# untitled.net
KiCad netlist of a schematic drawn in EAGLE
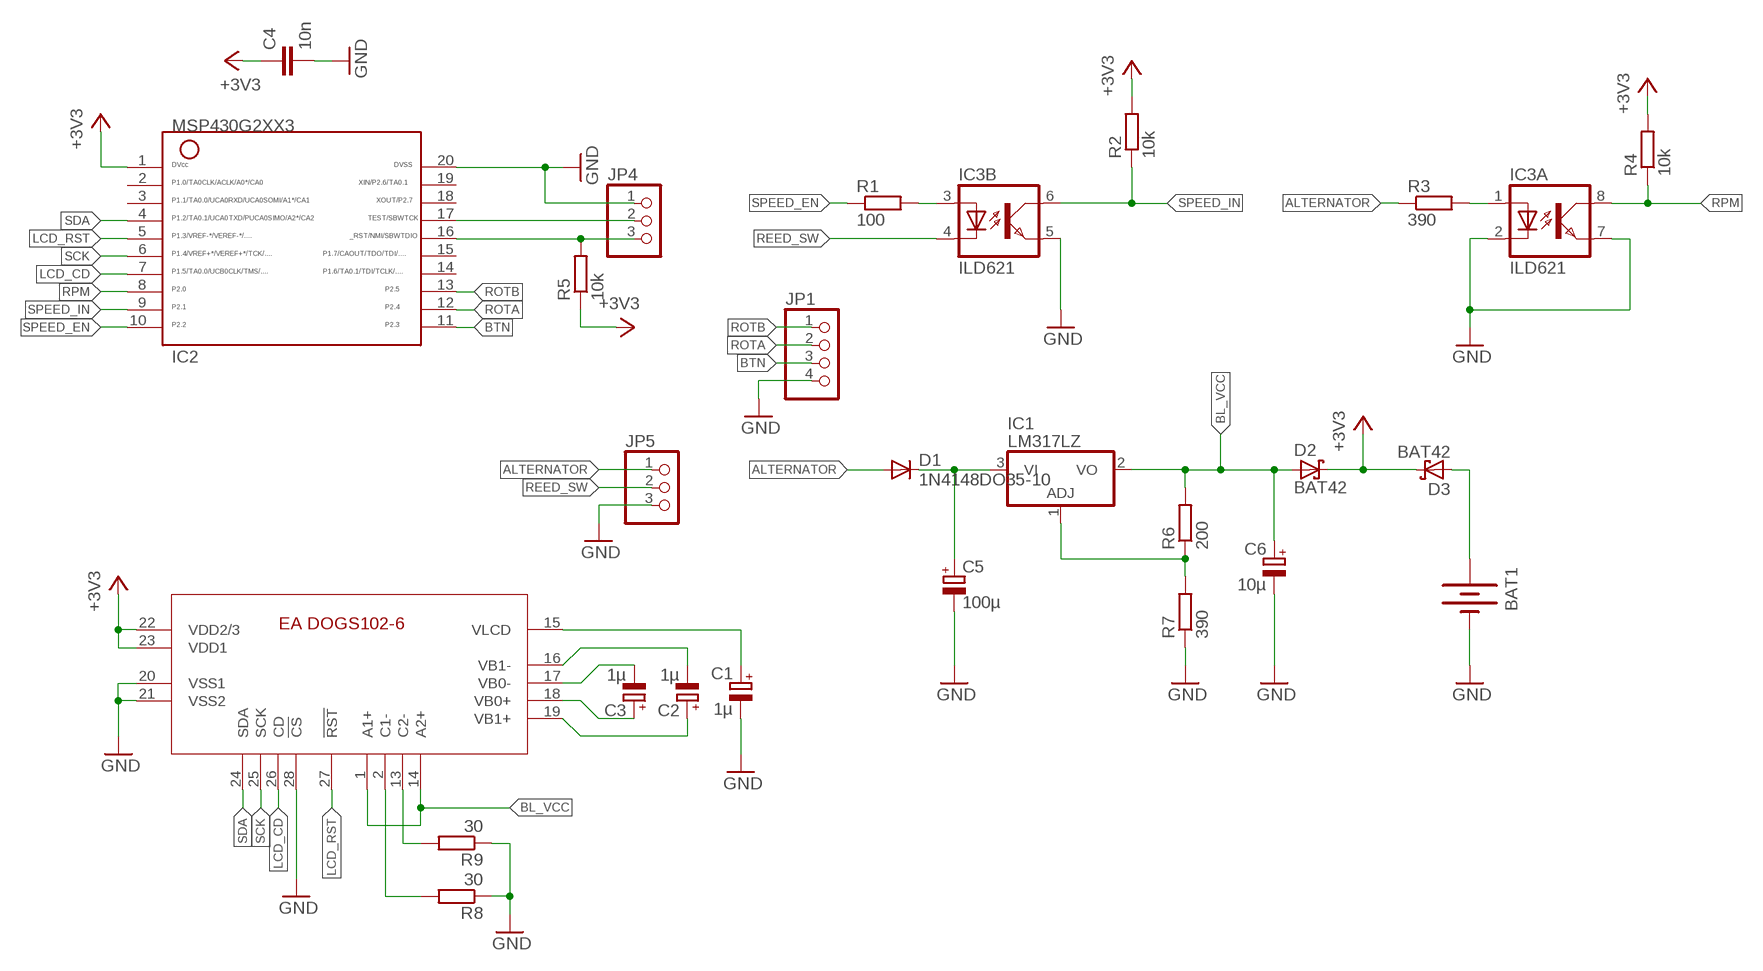
[diagram p0: schematic, sheet 1]

(export (version "E")
  (design (tool "Eeschema 10.0.6"))
  (components
    (comp (ref "BAT1")
      (value "BATTERY20PTH")
      (footprint "eagle-import:BATTCOM_20MM_PTH")
      (libsource (lib "eagle-import") (part "BATTERY20PTH"))
    )
    (comp (ref "C1")
      (value "1µ")
      (footprint "eagle-import:E2-4")
      (libsource (lib "eagle-import") (part "CPOL-EUE2-4"))
    )
    (comp (ref "C2")
      (value "1µ")
      (footprint "eagle-import:E2-4")
      (libsource (lib "eagle-import") (part "CPOL-EUE2-4"))
    )
    (comp (ref "C3")
      (value "1µ")
      (footprint "eagle-import:E2-4")
      (libsource (lib "eagle-import") (part "CPOL-EUE2-4"))
    )
    (comp (ref "C4")
      (value "10n")
      (footprint "eagle-import:C050-024X044")
      (libsource (lib "eagle-import") (part "C-EU050-024X044"))
    )
    (comp (ref "C5")
      (value "100µ")
      (footprint "eagle-import:E2,5-6E")
      (libsource (lib "eagle-import") (part "resistor_CPOL-EUE2,5-6E"))
    )
    (comp (ref "C6")
      (value "10µ")
      (footprint "eagle-import:E2-4")
      (libsource (lib "eagle-import") (part "CPOL-EUE2-4"))
    )
    (comp (ref "D1")
      (value "1N4148DO35-10")
      (footprint "eagle-import:DO35-10")
      (libsource (lib "eagle-import") (part "1N4148DO35-10"))
    )
    (comp (ref "D2")
      (value "BAT42")
      (footprint "eagle-import:DO35-10")
      (libsource (lib "eagle-import") (part "BAT42"))
    )
    (comp (ref "D3")
      (value "BAT42")
      (footprint "eagle-import:DO35-10")
      (libsource (lib "eagle-import") (part "BAT42"))
    )
    (comp (ref "IC1")
      (value "LM317LZ")
      (footprint "eagle-import:TO92")
      (libsource (lib "eagle-import") (part "317LZLM"))
    )
    (comp (ref "IC2")
      (value "G2XX3---N20")
      (footprint "eagle-import:N20")
      (libsource (lib "eagle-import") (part "G2XX3---N20"))
    )
    (comp (ref "IC3")
      (value "ILD621")
      (footprint "eagle-import:DIL08")
      (fields (field (name "MF") "VISHAY/TELEFUNKEN"))
      (libsource (lib "eagle-import") (part "ILD621"))
    )
    (comp (ref "JP1")
      (value "PINHD-1X4")
      (footprint "eagle-import:1X04")
      (libsource (lib "eagle-import") (part "PINHD-1X4"))
    )
    (comp (ref "JP4")
      (value "PINHD-1X3")
      (footprint "eagle-import:1X03")
      (libsource (lib "eagle-import") (part "PINHD-1X3"))
    )
    (comp (ref "JP5")
      (value "PINHD-1X3")
      (footprint "eagle-import:1X03")
      (libsource (lib "eagle-import") (part "PINHD-1X3"))
    )
    (comp (ref "R1")
      (value "100")
      (footprint "eagle-import:0204_7")
      (libsource (lib "eagle-import") (part "R-EU_0204/7"))
    )
    (comp (ref "R2")
      (value "10k")
      (footprint "eagle-import:0204_7")
      (libsource (lib "eagle-import") (part "R-EU_0204/7"))
    )
    (comp (ref "R3")
      (value "390")
      (footprint "eagle-import:0204_7")
      (libsource (lib "eagle-import") (part "R-EU_0204/7"))
    )
    (comp (ref "R4")
      (value "10k")
      (footprint "eagle-import:0204_7")
      (libsource (lib "eagle-import") (part "R-EU_0204/7"))
    )
    (comp (ref "R5")
      (value "10k")
      (footprint "eagle-import:0204_7")
      (libsource (lib "eagle-import") (part "R-EU_0204/7"))
    )
    (comp (ref "R6")
      (value "200")
      (footprint "eagle-import:0204_7")
      (libsource (lib "eagle-import") (part "R-EU_0204/7"))
    )
    (comp (ref "R7")
      (value "390")
      (footprint "eagle-import:0204_7")
      (libsource (lib "eagle-import") (part "R-EU_0204/7"))
    )
    (comp (ref "R8")
      (value "30")
      (footprint "eagle-import:0204_7")
      (libsource (lib "eagle-import") (part "R-EU_0204/7"))
    )
    (comp (ref "R9")
      (value "30")
      (footprint "eagle-import:0204_7")
      (libsource (lib "eagle-import") (part "R-EU_0204/7"))
    )
    (comp (ref "U$1")
      (value "EA-DOG102-6")
      (footprint "eagle-import:EA_DOGS102-6")
      (libsource (lib "eagle-import") (part "EA-DOG102-6"))
    )
  )
  (nets
    (net (code "1") (name "+3V3") (class "Default")
      (node (ref "C4") (pin "1") (pinfunction "1_1") (pintype "passive"))
      (node (ref "D2") (pin "C") (pinfunction "C_C") (pintype "passive"))
      (node (ref "D3") (pin "C") (pinfunction "C_C") (pintype "passive"))
      (node (ref "IC2") (pin "1") (pinfunction "1_1") (pintype "bidirectional"))
      (node (ref "R2") (pin "2") (pinfunction "2_2") (pintype "passive"))
      (node (ref "R4") (pin "2") (pinfunction "2_2") (pintype "passive"))
      (node (ref "R5") (pin "1") (pinfunction "1_1") (pintype "passive"))
      (node (ref "U$1") (pin "22") (pinfunction "VDD2/3_22") (pintype "power_in"))
      (node (ref "U$1") (pin "23") (pinfunction "VDD1_23") (pintype "power_in"))
    )
    (net (code "2") (name "ALTERNATOR") (class "Default")
      (node (ref "D1") (pin "A") (pinfunction "A_A") (pintype "passive"))
      (node (ref "JP5") (pin "1") (pinfunction "1_1") (pintype "passive"))
      (node (ref "R3") (pin "1") (pinfunction "1_1") (pintype "passive"))
    )
    (net (code "3") (name "BL_VCC") (class "Default")
      (node (ref "C6") (pin "+") (pinfunction "+_+") (pintype "passive"))
      (node (ref "D2") (pin "A") (pinfunction "A_A") (pintype "passive"))
      (node (ref "IC1") (pin "2") (pinfunction "VO_2") (pintype "passive"))
      (node (ref "R6") (pin "2") (pinfunction "2_2") (pintype "passive"))
      (node (ref "U$1") (pin "1") (pinfunction "A1+_1") (pintype "bidirectional"))
      (node (ref "U$1") (pin "14") (pinfunction "A2+_14") (pintype "bidirectional"))
    )
    (net (code "4") (name "BTN") (class "Default")
      (node (ref "IC2") (pin "11") (pinfunction "11_11") (pintype "bidirectional"))
      (node (ref "JP1") (pin "3") (pinfunction "3_3") (pintype "passive"))
    )
    (net (code "5") (name "GND") (class "Default")
      (node (ref "BAT1") (pin "2") (pinfunction "-_2") (pintype "power_in"))
      (node (ref "C1") (pin "-") (pinfunction "-_-") (pintype "passive"))
      (node (ref "C4") (pin "2") (pinfunction "2_2") (pintype "passive"))
      (node (ref "C5") (pin "-") (pinfunction "-_-") (pintype "passive"))
      (node (ref "C6") (pin "-") (pinfunction "-_-") (pintype "passive"))
      (node (ref "IC2") (pin "20") (pinfunction "20_20") (pintype "bidirectional"))
      (node (ref "IC3") (pin "2") (pinfunction "C_2") (pintype "passive"))
      (node (ref "IC3") (pin "5") (pinfunction "EMIT_5") (pintype "passive"))
      (node (ref "IC3") (pin "7") (pinfunction "EMIT_7") (pintype "passive"))
      (node (ref "JP1") (pin "4") (pinfunction "4_4") (pintype "passive"))
      (node (ref "JP4") (pin "1") (pinfunction "1_1") (pintype "passive"))
      (node (ref "JP5") (pin "3") (pinfunction "3_3") (pintype "passive"))
      (node (ref "R7") (pin "1") (pinfunction "1_1") (pintype "passive"))
      (node (ref "R8") (pin "1") (pinfunction "1_1") (pintype "passive"))
      (node (ref "R9") (pin "1") (pinfunction "1_1") (pintype "passive"))
      (node (ref "U$1") (pin "20") (pinfunction "VSS1_20") (pintype "power_in"))
      (node (ref "U$1") (pin "21") (pinfunction "VSS2_21") (pintype "power_in"))
      (node (ref "U$1") (pin "28") (pinfunction "~{CS}_28") (pintype "bidirectional"))
    )
    (net (code "6") (name "LCD_CD") (class "Default")
      (node (ref "IC2") (pin "7") (pinfunction "7_7") (pintype "bidirectional"))
      (node (ref "U$1") (pin "26") (pinfunction "CD_26") (pintype "bidirectional"))
    )
    (net (code "7") (name "LCD_RST") (class "Default")
      (node (ref "IC2") (pin "5") (pinfunction "5_5") (pintype "bidirectional"))
      (node (ref "U$1") (pin "27") (pinfunction "~{RST}_27") (pintype "bidirectional"))
    )
    (net (code "8") (name "Net-(BAT1-+)") (class "Default")
      (node (ref "BAT1") (pin "1") (pinfunction "+_1") (pintype "power_in"))
      (node (ref "D3") (pin "A") (pinfunction "A_A") (pintype "passive"))
    )
    (net (code "9") (name "Net-(IC1-ADJ)") (class "Default")
      (node (ref "IC1") (pin "1") (pinfunction "ADJ_1") (pintype "input"))
      (node (ref "R6") (pin "1") (pinfunction "1_1") (pintype "passive"))
      (node (ref "R7") (pin "2") (pinfunction "2_2") (pintype "passive"))
    )
    (net (code "10") (name "Net-(IC1-VI)") (class "Default")
      (node (ref "C5") (pin "+") (pinfunction "+_+") (pintype "passive"))
      (node (ref "D1") (pin "C") (pinfunction "C_C") (pintype "passive"))
      (node (ref "IC1") (pin "3") (pinfunction "VI_3") (pintype "input"))
    )
    (net (code "11") (name "Net-(IC2-Pad16)") (class "Default")
      (node (ref "IC2") (pin "16") (pinfunction "16_16") (pintype "bidirectional"))
      (node (ref "JP4") (pin "3") (pinfunction "3_3") (pintype "passive"))
      (node (ref "R5") (pin "2") (pinfunction "2_2") (pintype "passive"))
    )
    (net (code "12") (name "Net-(IC2-Pad17)") (class "Default")
      (node (ref "IC2") (pin "17") (pinfunction "17_17") (pintype "bidirectional"))
      (node (ref "JP4") (pin "2") (pinfunction "2_2") (pintype "passive"))
    )
    (net (code "13") (name "Net-(IC3A-A)") (class "Default")
      (node (ref "IC3") (pin "1") (pinfunction "A_1") (pintype "passive"))
      (node (ref "R3") (pin "2") (pinfunction "2_2") (pintype "passive"))
    )
    (net (code "14") (name "Net-(IC3B-A)") (class "Default")
      (node (ref "IC3") (pin "3") (pinfunction "A_3") (pintype "passive"))
      (node (ref "R1") (pin "2") (pinfunction "2_2") (pintype "passive"))
    )
    (net (code "15") (name "Net-(U$1-C1-)") (class "Default")
      (node (ref "R8") (pin "2") (pinfunction "2_2") (pintype "passive"))
      (node (ref "U$1") (pin "2") (pinfunction "C1-_2") (pintype "bidirectional"))
    )
    (net (code "16") (name "Net-(U$1-C2-)") (class "Default")
      (node (ref "R9") (pin "2") (pinfunction "2_2") (pintype "passive"))
      (node (ref "U$1") (pin "13") (pinfunction "C2-_13") (pintype "bidirectional"))
    )
    (net (code "17") (name "Net-(U$1-VB0+)") (class "Default")
      (node (ref "C3") (pin "+") (pinfunction "+_+") (pintype "passive"))
      (node (ref "U$1") (pin "18") (pinfunction "VB0+_18") (pintype "bidirectional"))
    )
    (net (code "18") (name "Net-(U$1-VB0-)") (class "Default")
      (node (ref "C3") (pin "-") (pinfunction "-_-") (pintype "passive"))
      (node (ref "U$1") (pin "17") (pinfunction "VB0-_17") (pintype "bidirectional"))
    )
    (net (code "19") (name "Net-(U$1-VB1+)") (class "Default")
      (node (ref "C2") (pin "+") (pinfunction "+_+") (pintype "passive"))
      (node (ref "U$1") (pin "19") (pinfunction "VB1+_19") (pintype "bidirectional"))
    )
    (net (code "20") (name "Net-(U$1-VB1-)") (class "Default")
      (node (ref "C2") (pin "-") (pinfunction "-_-") (pintype "passive"))
      (node (ref "U$1") (pin "16") (pinfunction "VB1-_16") (pintype "bidirectional"))
    )
    (net (code "21") (name "Net-(U$1-VLCD)") (class "Default")
      (node (ref "C1") (pin "+") (pinfunction "+_+") (pintype "passive"))
      (node (ref "U$1") (pin "15") (pinfunction "VLCD_15") (pintype "bidirectional"))
    )
    (net (code "22") (name "REED_SW") (class "Default")
      (node (ref "IC3") (pin "4") (pinfunction "C_4") (pintype "passive"))
      (node (ref "JP5") (pin "2") (pinfunction "2_2") (pintype "passive"))
    )
    (net (code "23") (name "ROTA") (class "Default")
      (node (ref "IC2") (pin "12") (pinfunction "12_12") (pintype "bidirectional"))
      (node (ref "JP1") (pin "2") (pinfunction "2_2") (pintype "passive"))
    )
    (net (code "24") (name "ROTB") (class "Default")
      (node (ref "IC2") (pin "13") (pinfunction "13_13") (pintype "bidirectional"))
      (node (ref "JP1") (pin "1") (pinfunction "1_1") (pintype "passive"))
    )
    (net (code "25") (name "RPM") (class "Default")
      (node (ref "IC2") (pin "8") (pinfunction "8_8") (pintype "bidirectional"))
      (node (ref "IC3") (pin "8") (pinfunction "COL_8") (pintype "passive"))
      (node (ref "R4") (pin "1") (pinfunction "1_1") (pintype "passive"))
    )
    (net (code "26") (name "SCK") (class "Default")
      (node (ref "IC2") (pin "6") (pinfunction "6_6") (pintype "bidirectional"))
      (node (ref "U$1") (pin "25") (pinfunction "SCK_25") (pintype "bidirectional"))
    )
    (net (code "27") (name "SDA") (class "Default")
      (node (ref "IC2") (pin "4") (pinfunction "4_4") (pintype "bidirectional"))
      (node (ref "U$1") (pin "24") (pinfunction "SDA_24") (pintype "bidirectional"))
    )
    (net (code "28") (name "SPEED_EN") (class "Default")
      (node (ref "IC2") (pin "10") (pinfunction "10_10") (pintype "bidirectional"))
      (node (ref "R1") (pin "1") (pinfunction "1_1") (pintype "passive"))
    )
    (net (code "29") (name "SPEED_IN") (class "Default")
      (node (ref "IC2") (pin "9") (pinfunction "9_9") (pintype "bidirectional"))
      (node (ref "IC3") (pin "6") (pinfunction "COL_6") (pintype "passive"))
      (node (ref "R2") (pin "1") (pinfunction "1_1") (pintype "passive"))
    )
    (net (code "30") (name "unconnected-(IC2-Pad2)") (class "Default")
      (node (ref "IC2") (pin "2") (pinfunction "2_2") (pintype "bidirectional"))
    )
    (net (code "31") (name "unconnected-(IC2-Pad3)") (class "Default")
      (node (ref "IC2") (pin "3") (pinfunction "3_3") (pintype "bidirectional"))
    )
    (net (code "32") (name "unconnected-(IC2-Pad14)") (class "Default")
      (node (ref "IC2") (pin "14") (pinfunction "14_14") (pintype "bidirectional"))
    )
    (net (code "33") (name "unconnected-(IC2-Pad15)") (class "Default")
      (node (ref "IC2") (pin "15") (pinfunction "15_15") (pintype "bidirectional"))
    )
    (net (code "34") (name "unconnected-(IC2-Pad18)") (class "Default")
      (node (ref "IC2") (pin "18") (pinfunction "18_18") (pintype "bidirectional"))
    )
    (net (code "35") (name "unconnected-(IC2-Pad19)") (class "Default")
      (node (ref "IC2") (pin "19") (pinfunction "19_19") (pintype "bidirectional"))
    )
  )
)
